# blink1mk2_v2c3.net
KiCad netlist of a schematic drawn in EAGLE
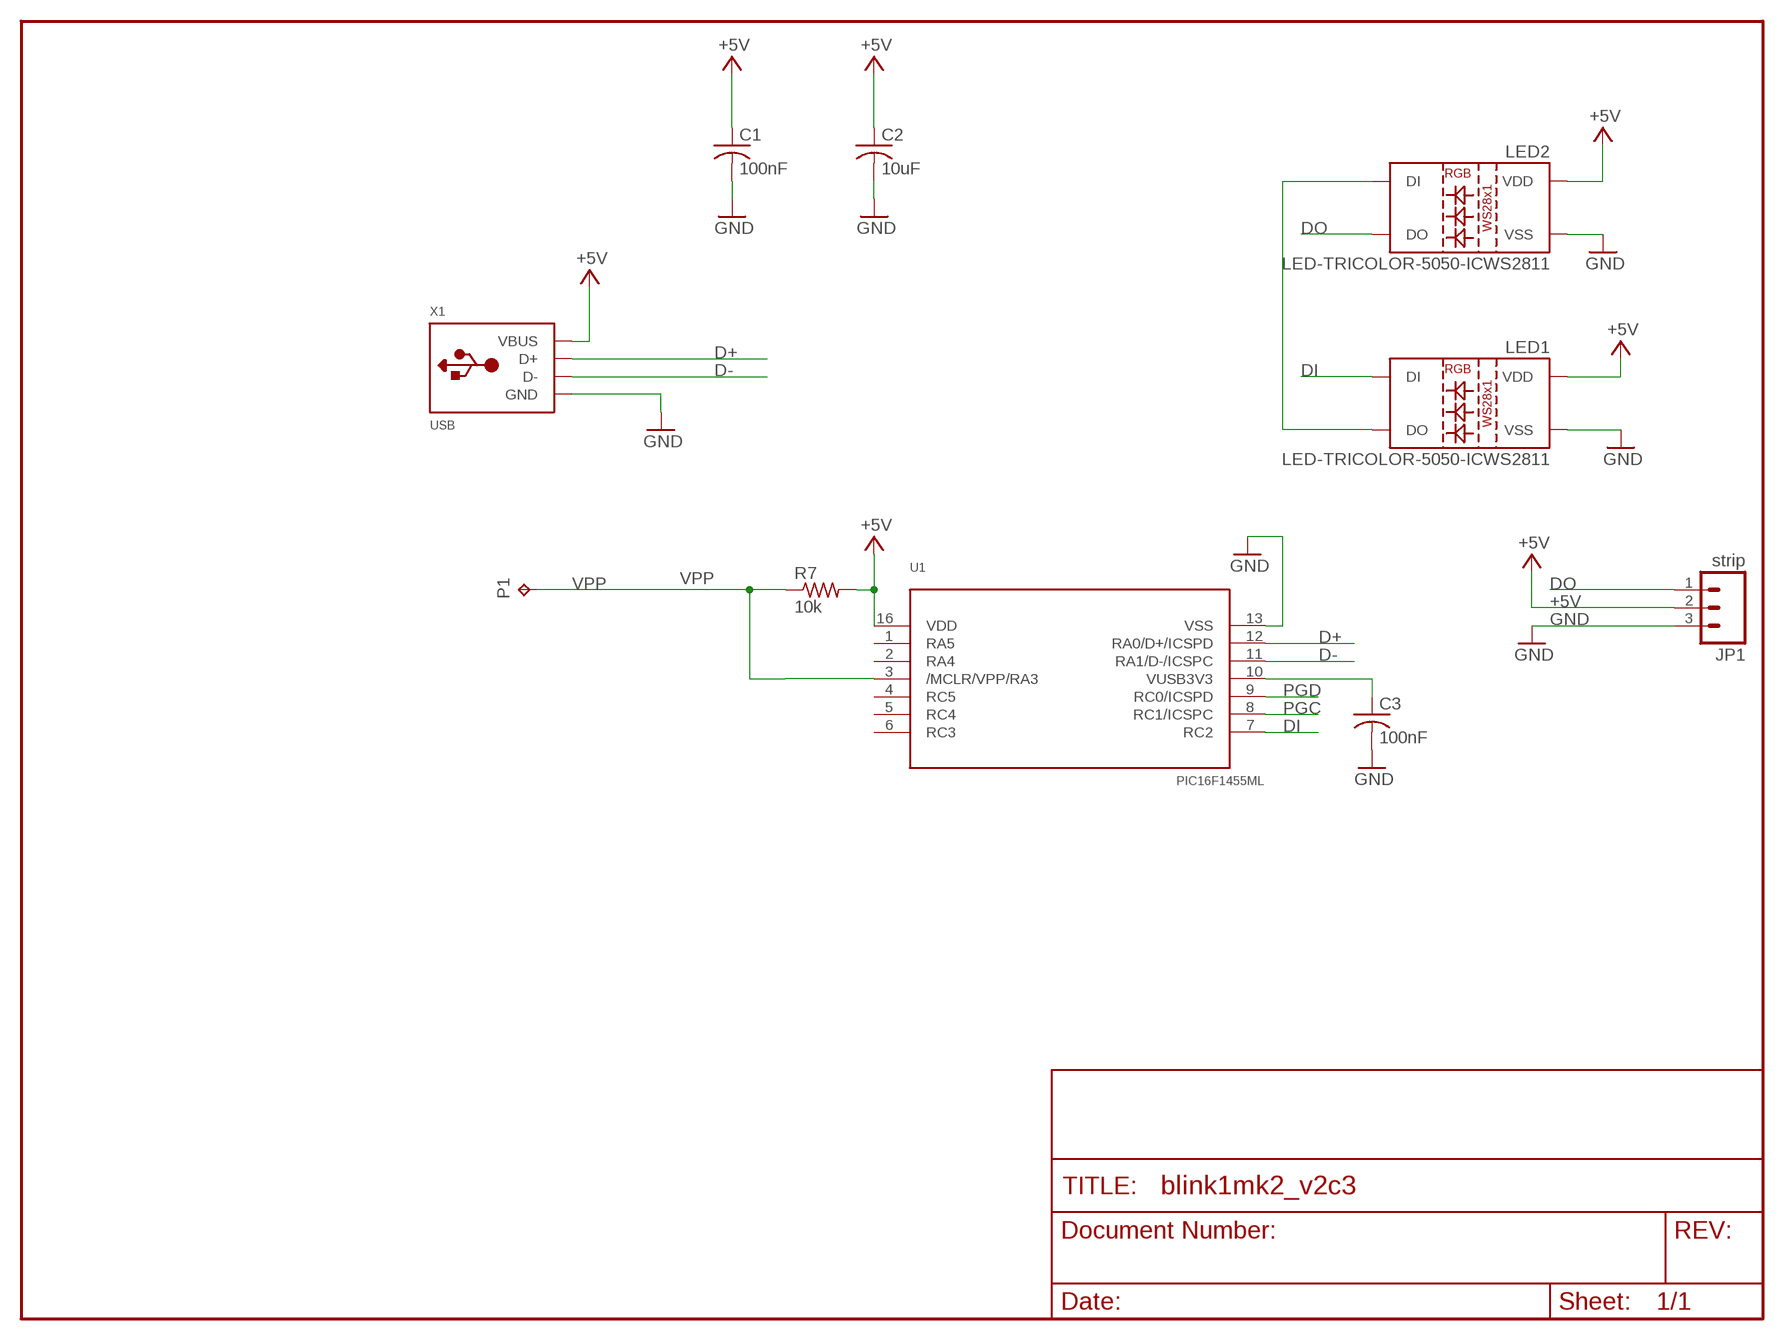
[diagram p0: schematic, sheet 1]

(export (version "E")
  (design (tool "Eeschema 10.0.6"))
  (components
    (comp (ref "C1")
      (value "100nF")
      (footprint "eagle-import:C0603")
      (libsource (lib "eagle-import") (part "C-USC0603"))
    )
    (comp (ref "C2")
      (value "10uF")
      (footprint "eagle-import:C0603")
      (libsource (lib "eagle-import") (part "C-USC0603"))
    )
    (comp (ref "C3")
      (value "100nF")
      (footprint "eagle-import:C0603")
      (libsource (lib "eagle-import") (part "C-USC0603"))
    )
    (comp (ref "JP1")
      (value "strip")
      (footprint "eagle-import:1X03")
      (libsource (lib "eagle-import") (part "M03PTH"))
    )
    (comp (ref "LED1")
      (value "LED-TRICOLOR-5050-ICWS2811")
      (footprint "eagle-import:LED-TRICOLOR-5050-IC")
      (libsource (lib "eagle-import") (part "LED-TRICOLOR-5050-ICWS2811"))
    )
    (comp (ref "LED2")
      (value "LED-TRICOLOR-5050-ICWS2811")
      (footprint "eagle-import:LED-TRICOLOR-5050-IC")
      (libsource (lib "eagle-import") (part "LED-TRICOLOR-5050-ICWS2811"))
    )
    (comp (ref "P1")
      (value "TPTP11SQ")
      (footprint "eagle-import:TP11SQ")
      (libsource (lib "eagle-import") (part "TPTP11SQ"))
    )
    (comp (ref "R7")
      (value "10k")
      (footprint "eagle-import:R0603")
      (libsource (lib "eagle-import") (part "R-US_R0603"))
    )
    (comp (ref "U1")
      (value "PIC16F1455ML")
      (footprint "eagle-import:QFN16_4X4")
      (libsource (lib "eagle-import") (part "PIC16F1455ML"))
    )
    (comp (ref "X1")
      (value "USB")
      (footprint "eagle-import:MOLEX-48037-1000")
      (libsource (lib "eagle-import") (part "USB"))
    )
  )
  (nets
    (net (code "1") (name "+5V") (class "Default")
      (node (ref "C1") (pin "1") (pinfunction "1_1") (pintype "passive"))
      (node (ref "C2") (pin "1") (pinfunction "1_1") (pintype "passive"))
      (node (ref "JP1") (pin "2") (pinfunction "2_2") (pintype "passive"))
      (node (ref "LED1") (pin "3") (pinfunction "VDD_3") (pintype "bidirectional"))
      (node (ref "LED1") (pin "5") (pinfunction "VDD_5") (pintype "bidirectional"))
      (node (ref "LED2") (pin "3") (pinfunction "VDD_3") (pintype "bidirectional"))
      (node (ref "LED2") (pin "5") (pinfunction "VDD_5") (pintype "bidirectional"))
      (node (ref "R7") (pin "2") (pinfunction "2_2") (pintype "passive"))
      (node (ref "U1") (pin "16") (pinfunction "VDD_16") (pintype "bidirectional"))
      (node (ref "X1") (pin "1") (pinfunction "VBUS_1") (pintype "power_in"))
    )
    (net (code "2") (name "/D+") (class "Default")
      (node (ref "U1") (pin "12") (pinfunction "RA0/D+/ICSPD_12") (pintype "bidirectional"))
      (node (ref "X1") (pin "3") (pinfunction "D+_3") (pintype "bidirectional"))
    )
    (net (code "3") (name "/D-") (class "Default")
      (node (ref "U1") (pin "11") (pinfunction "RA1/D-/ICSPC_11") (pintype "bidirectional"))
      (node (ref "X1") (pin "2") (pinfunction "D-_2") (pintype "bidirectional"))
    )
    (net (code "4") (name "/DI") (class "Default")
      (node (ref "LED1") (pin "2") (pinfunction "DI_2") (pintype "bidirectional"))
      (node (ref "U1") (pin "7") (pinfunction "RC2_7") (pintype "bidirectional"))
    )
    (net (code "5") (name "/DO") (class "Default")
      (node (ref "JP1") (pin "1") (pinfunction "1_1") (pintype "passive"))
      (node (ref "LED2") (pin "1") (pinfunction "DO_1") (pintype "bidirectional"))
    )
    (net (code "6") (name "/PGC") (class "Default")
      (node (ref "U1") (pin "8") (pinfunction "RC1/ICSPC_8") (pintype "bidirectional"))
    )
    (net (code "7") (name "/PGD") (class "Default")
      (node (ref "U1") (pin "9") (pinfunction "RC0/ICSPD_9") (pintype "bidirectional"))
    )
    (net (code "8") (name "/VPP") (class "Default")
      (node (ref "P1") (pin "TP") (pinfunction "TP_TP") (pintype "input"))
      (node (ref "R7") (pin "1") (pinfunction "1_1") (pintype "passive"))
      (node (ref "U1") (pin "3") (pinfunction "/MCLR/VPP/RA3_3") (pintype "bidirectional"))
    )
    (net (code "9") (name "GND") (class "Default")
      (node (ref "C1") (pin "2") (pinfunction "2_2") (pintype "passive"))
      (node (ref "C2") (pin "2") (pinfunction "2_2") (pintype "passive"))
      (node (ref "C3") (pin "2") (pinfunction "2_2") (pintype "passive"))
      (node (ref "JP1") (pin "3") (pinfunction "3_3") (pintype "passive"))
      (node (ref "LED1") (pin "6") (pinfunction "VSS_6") (pintype "bidirectional"))
      (node (ref "LED2") (pin "6") (pinfunction "VSS_6") (pintype "bidirectional"))
      (node (ref "U1") (pin "13") (pinfunction "VSS_13") (pintype "bidirectional"))
      (node (ref "X1") (pin "4") (pinfunction "GND_4") (pintype "power_in"))
    )
    (net (code "10") (name "Net-(LED1-DO)") (class "Default")
      (node (ref "LED1") (pin "1") (pinfunction "DO_1") (pintype "bidirectional"))
      (node (ref "LED2") (pin "2") (pinfunction "DI_2") (pintype "bidirectional"))
    )
    (net (code "11") (name "Net-(U1-VUSB3V3)") (class "Default")
      (node (ref "C3") (pin "1") (pinfunction "1_1") (pintype "passive"))
      (node (ref "U1") (pin "10") (pinfunction "VUSB3V3_10") (pintype "bidirectional"))
    )
    (net (code "12") (name "unconnected-(U1-RA4-Pad2)") (class "Default")
      (node (ref "U1") (pin "2") (pinfunction "RA4_2") (pintype "bidirectional"))
    )
    (net (code "13") (name "unconnected-(U1-RA5-Pad1)") (class "Default")
      (node (ref "U1") (pin "1") (pinfunction "RA5_1") (pintype "bidirectional"))
    )
    (net (code "14") (name "unconnected-(U1-RC3-Pad6)") (class "Default")
      (node (ref "U1") (pin "6") (pinfunction "RC3_6") (pintype "bidirectional"))
    )
    (net (code "15") (name "unconnected-(U1-RC4-Pad5)") (class "Default")
      (node (ref "U1") (pin "5") (pinfunction "RC4_5") (pintype "bidirectional"))
    )
    (net (code "16") (name "unconnected-(U1-RC5-Pad4)") (class "Default")
      (node (ref "U1") (pin "4") (pinfunction "RC5_4") (pintype "bidirectional"))
    )
  )
)
